# USB.net
KiCad netlist of a schematic drawn in Altium Designer
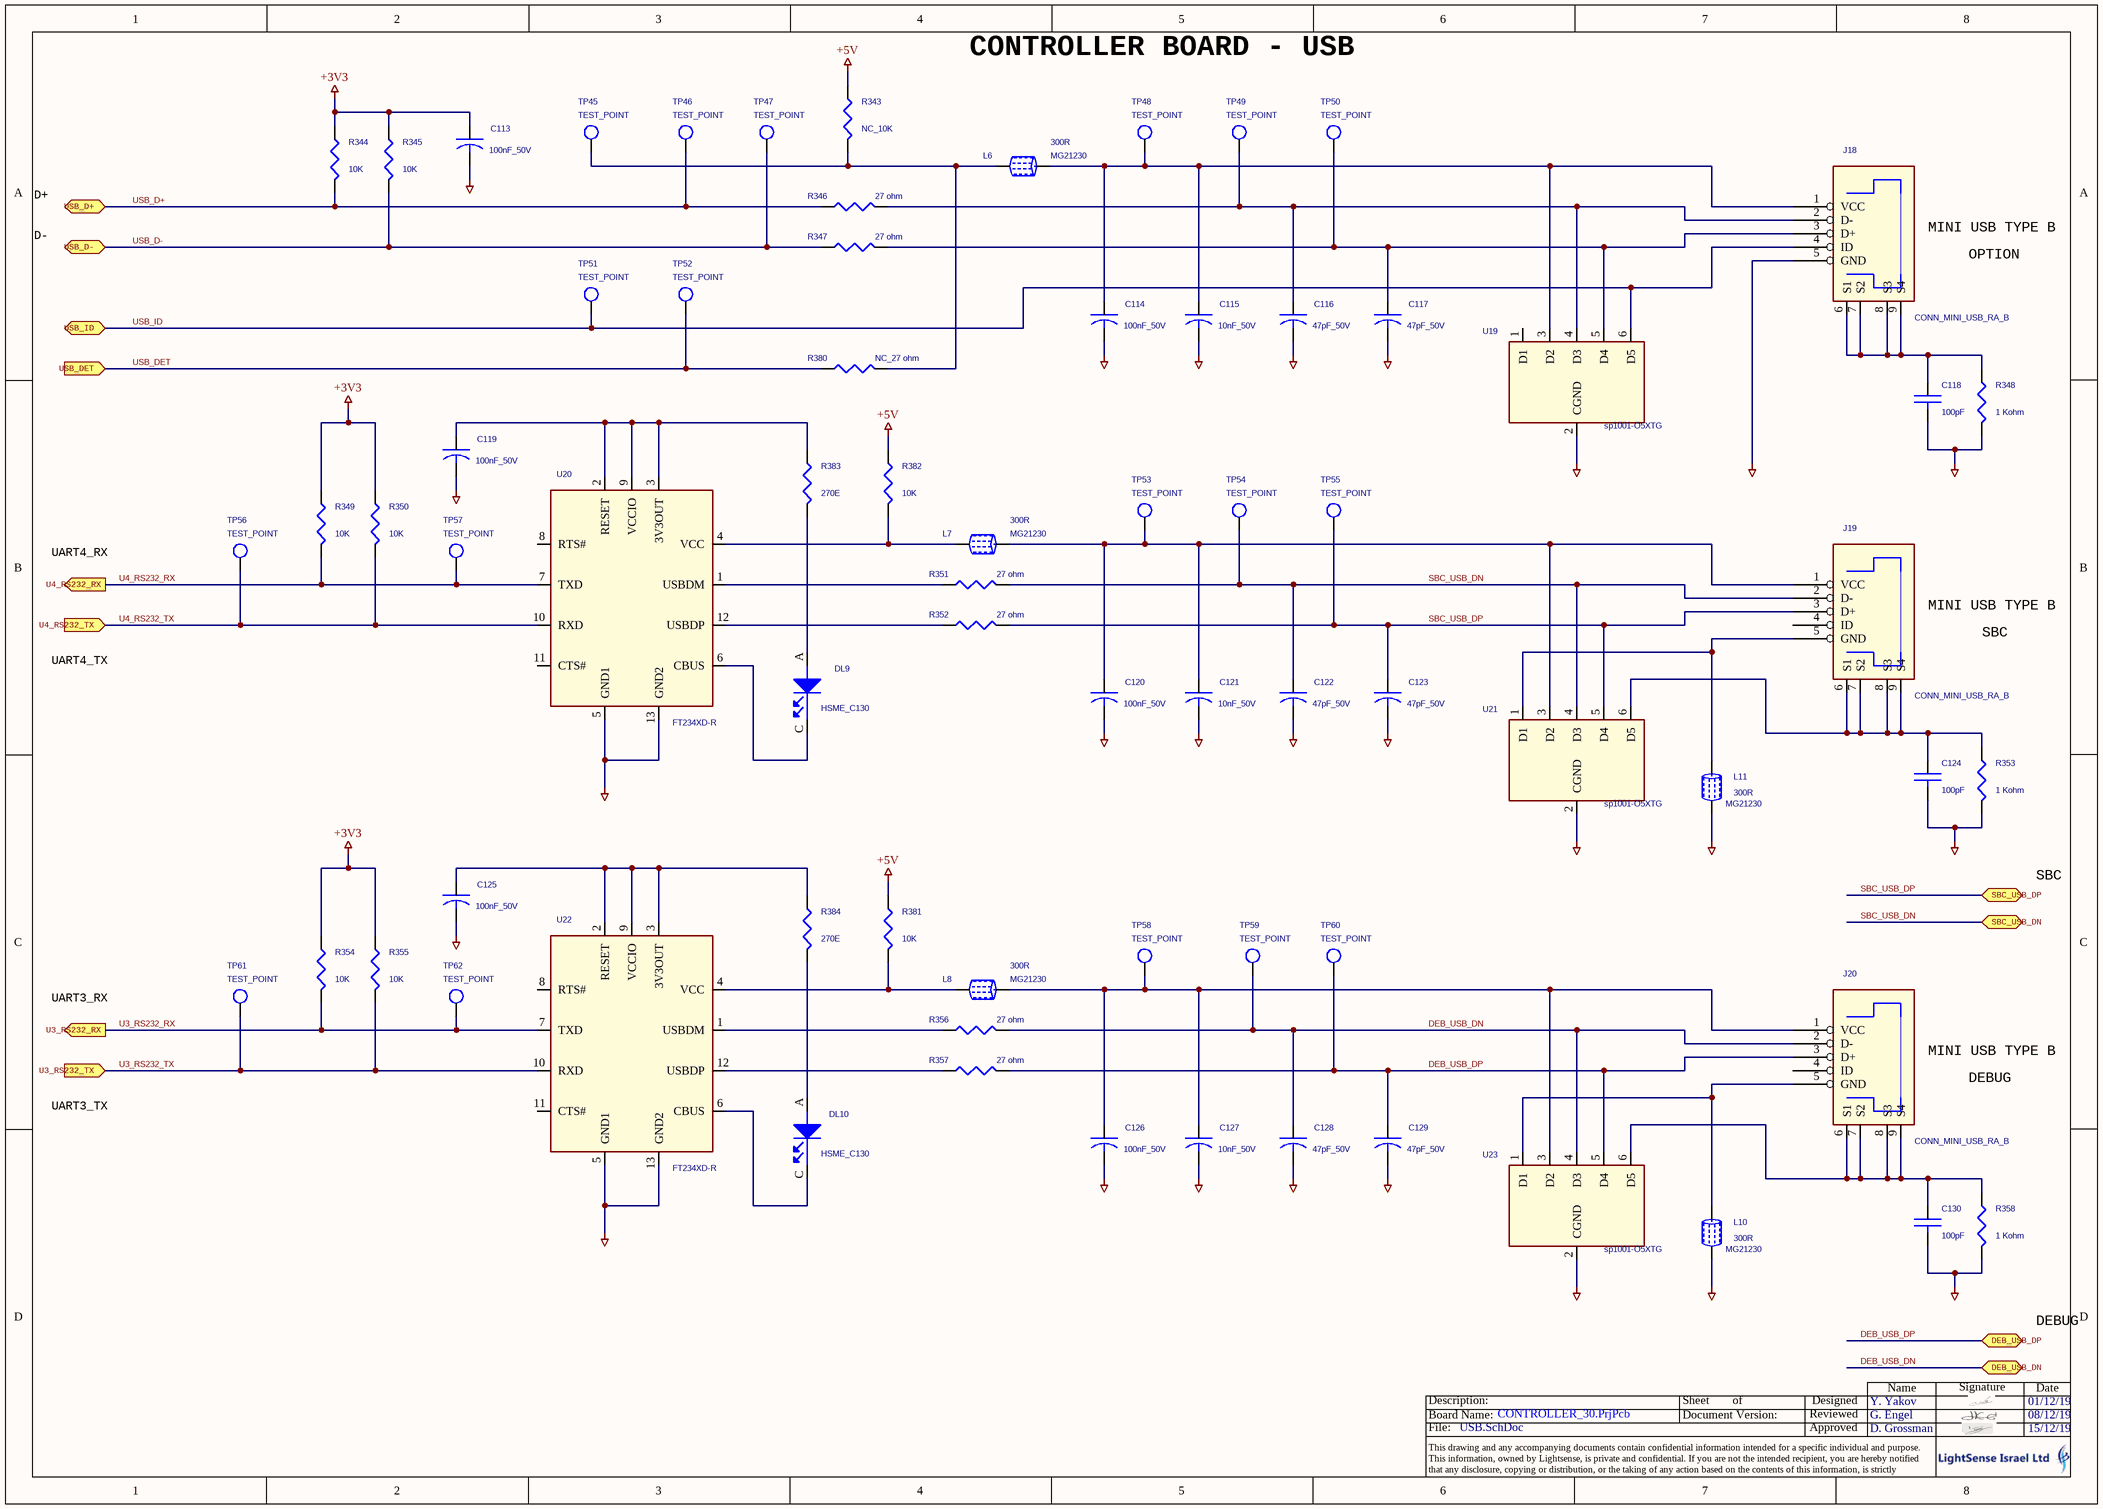
[diagram p0: USB.SchDoc]

(export (version "E")
  (design (tool "Eeschema 10.0.6"))
  (components
    (comp (ref "C113")
      (value "100nF_50V")
      (footprint "0603")
      (description "CAP_SMT_0603_50V_X7R_10%")
      (fields (field (name "MFG") "KEMET"))
      (libsource (lib "*") (part "C"))
    )
    (comp (ref "C114")
      (value "100nF_50V")
      (footprint "0603")
      (description "CAP_SMT_0603_50V_X7R_10%")
      (fields (field (name "MFG") "KEMET"))
      (libsource (lib "*") (part "C"))
    )
    (comp (ref "C115")
      (value "10nF_50V")
      (footprint "0603")
      (description "CAP_SMT_0603_50V_X7R_10%")
      (fields (field (name "MFG") "KEMET"))
      (libsource (lib "*") (part "C"))
    )
    (comp (ref "C116")
      (value "47pF_50V")
      (footprint "0603")
      (description "CAP_SMT_0603_50V_X7R_10%")
      (fields (field (name "MFG") "KEMET"))
      (libsource (lib "*") (part "C"))
    )
    (comp (ref "C117")
      (value "47pF_50V")
      (footprint "0603")
      (description "CAP_SMT_0603_50V_X7R_10%")
      (fields (field (name "MFG") "KEMET"))
      (libsource (lib "*") (part "C"))
    )
    (comp (ref "C118")
      (value "100pF")
      (footprint "C1206")
      (description "Cap cer 100pF 5% 500V C0G 1206 smd")
      (fields (field (name "PART_NUMBER") "CP70050"))
      (libsource (lib "*") (part "C1206"))
    )
    (comp (ref "C119")
      (value "100nF_50V")
      (footprint "0603")
      (description "CAP_SMT_0603_50V_X7R_10%")
      (fields (field (name "MFG") "KEMET"))
      (libsource (lib "*") (part "C"))
    )
    (comp (ref "C120")
      (value "100nF_50V")
      (footprint "0603")
      (description "CAP_SMT_0603_50V_X7R_10%")
      (fields (field (name "MFG") "KEMET"))
      (libsource (lib "*") (part "C"))
    )
    (comp (ref "C121")
      (value "10nF_50V")
      (footprint "0603")
      (description "CAP_SMT_0603_50V_X7R_10%")
      (fields (field (name "MFG") "KEMET"))
      (libsource (lib "*") (part "C"))
    )
    (comp (ref "C122")
      (value "47pF_50V")
      (footprint "0603")
      (description "CAP_SMT_0603_50V_X7R_10%")
      (fields (field (name "MFG") "KEMET"))
      (libsource (lib "*") (part "C"))
    )
    (comp (ref "C123")
      (value "47pF_50V")
      (footprint "0603")
      (description "CAP_SMT_0603_50V_X7R_10%")
      (fields (field (name "MFG") "KEMET"))
      (libsource (lib "*") (part "C"))
    )
    (comp (ref "C124")
      (value "100pF")
      (footprint "C1206")
      (description "Cap cer 100pF 5% 500V C0G 1206 smd")
      (fields (field (name "PART_NUMBER") "CP70050"))
      (libsource (lib "*") (part "C1206"))
    )
    (comp (ref "C125")
      (value "100nF_50V")
      (footprint "0603")
      (description "CAP_SMT_0603_50V_X7R_10%")
      (fields (field (name "MFG") "KEMET"))
      (libsource (lib "*") (part "C"))
    )
    (comp (ref "C126")
      (value "100nF_50V")
      (footprint "0603")
      (description "CAP_SMT_0603_50V_X7R_10%")
      (fields (field (name "MFG") "KEMET"))
      (libsource (lib "*") (part "C"))
    )
    (comp (ref "C127")
      (value "10nF_50V")
      (footprint "0603")
      (description "CAP_SMT_0603_50V_X7R_10%")
      (fields (field (name "MFG") "KEMET"))
      (libsource (lib "*") (part "C"))
    )
    (comp (ref "C128")
      (value "47pF_50V")
      (footprint "0603")
      (description "CAP_SMT_0603_50V_X7R_10%")
      (fields (field (name "MFG") "KEMET"))
      (libsource (lib "*") (part "C"))
    )
    (comp (ref "C129")
      (value "47pF_50V")
      (footprint "0603")
      (description "CAP_SMT_0603_50V_X7R_10%")
      (fields (field (name "MFG") "KEMET"))
      (libsource (lib "*") (part "C"))
    )
    (comp (ref "C130")
      (value "100pF")
      (footprint "C1206")
      (description "Cap cer 100pF 5% 500V C0G 1206 smd")
      (fields (field (name "PART_NUMBER") "CP70050"))
      (libsource (lib "*") (part "C1206"))
    )
    (comp (ref "DL9")
      (value "HSME_C130")
      (footprint "LED_0603")
      (fields (field (name "MFG") "AVAGO"))
      (libsource (lib "*") (part "LED"))
    )
    (comp (ref "DL10")
      (value "HSME_C130")
      (footprint "LED_0603")
      (fields (field (name "MFG") "AVAGO"))
      (libsource (lib "*") (part "LED"))
    )
    (comp (ref "J18")
      (value "CONN_MINI_USB_RA_B")
      (footprint "MUSB_B_9PIN")
      (fields (field (name "MFG") "SAMTEC"))
      (libsource (lib "*") (part "CONN_MINI_USB_RA_B"))
    )
    (comp (ref "J19")
      (value "CONN_MINI_USB_RA_B")
      (footprint "MUSB_B_9PIN")
      (fields (field (name "MFG") "SAMTEC"))
      (libsource (lib "*") (part "CONN_MINI_USB_RA_B"))
    )
    (comp (ref "J20")
      (value "CONN_MINI_USB_RA_B")
      (footprint "MUSB_B_9PIN")
      (fields (field (name "MFG") "SAMTEC"))
      (libsource (lib "*") (part "CONN_MINI_USB_RA_B"))
    )
    (comp (ref "L6")
      (value "300R")
      (footprint "B0603")
      (description "Chip Bead Z 300 Ohm 0603 RoHS")
      (fields (field (name "PART_NUMBER") "MG21230"))
      (libsource (lib "*") (part "FERRITE BEAD2_0"))
    )
    (comp (ref "L7")
      (value "300R")
      (footprint "B0603")
      (description "Chip Bead Z 300 Ohm 0603 RoHS")
      (fields (field (name "PART_NUMBER") "MG21230"))
      (libsource (lib "*") (part "FERRITE BEAD2_0"))
    )
    (comp (ref "L8")
      (value "300R")
      (footprint "B0603")
      (description "Chip Bead Z 300 Ohm 0603 RoHS")
      (fields (field (name "PART_NUMBER") "MG21230"))
      (libsource (lib "*") (part "FERRITE BEAD2_0"))
    )
    (comp (ref "L10")
      (value "300R")
      (footprint "B0603")
      (description "Chip Bead Z 300 Ohm 0603 RoHS")
      (fields (field (name "PART_NUMBER") "MG21230"))
      (libsource (lib "*") (part "FERRITE BEAD2_0"))
    )
    (comp (ref "L11")
      (value "300R")
      (footprint "B0603")
      (description "Chip Bead Z 300 Ohm 0603 RoHS")
      (fields (field (name "PART_NUMBER") "MG21230"))
      (libsource (lib "*") (part "FERRITE BEAD2_0"))
    )
    (comp (ref "R343")
      (value "NC_10K")
      (footprint "0603")
      (fields (field (name "MFG") "YAGEO"))
      (libsource (lib "*") (part "R_Dup1"))
    )
    (comp (ref "R344")
      (value "10K")
      (footprint "0603")
      (fields (field (name "MFG") "YAGEO"))
      (libsource (lib "*") (part "R_Dup1"))
    )
    (comp (ref "R345")
      (value "10K")
      (footprint "0603")
      (fields (field (name "MFG") "YAGEO"))
      (libsource (lib "*") (part "R_Dup1"))
    )
    (comp (ref "R346")
      (value "27 ohm")
      (footprint "R0603")
      (description "Res 330 Ohm 5% 0603 RoHS")
      (fields (field (name "PART_NUMBER") "RS61410"))
      (libsource (lib "*") (part "R0603"))
    )
    (comp (ref "R347")
      (value "27 ohm")
      (footprint "R0603")
      (description "Res 330 Ohm 5% 0603 RoHS")
      (fields (field (name "PART_NUMBER") "RS61410"))
      (libsource (lib "*") (part "R0603"))
    )
    (comp (ref "R348")
      (value "1 Kohm")
      (footprint "R1206")
      (description "RES 1 Kohm 1% 1206 RoHS")
      (fields (field (name "PART_NUMBER") "RS00940"))
      (libsource (lib "*") (part "R1206"))
    )
    (comp (ref "R349")
      (value "10K")
      (footprint "0603")
      (fields (field (name "MFG") "YAGEO"))
      (libsource (lib "*") (part "R_Dup1"))
    )
    (comp (ref "R350")
      (value "10K")
      (footprint "0603")
      (fields (field (name "MFG") "YAGEO"))
      (libsource (lib "*") (part "R_Dup1"))
    )
    (comp (ref "R351")
      (value "27 ohm")
      (footprint "R0603")
      (description "Res 330 Ohm 5% 0603 RoHS")
      (fields (field (name "PART_NUMBER") "RS61410"))
      (libsource (lib "*") (part "R0603"))
    )
    (comp (ref "R352")
      (value "27 ohm")
      (footprint "R0603")
      (description "Res 330 Ohm 5% 0603 RoHS")
      (fields (field (name "PART_NUMBER") "RS61410"))
      (libsource (lib "*") (part "R0603"))
    )
    (comp (ref "R353")
      (value "1 Kohm")
      (footprint "R1206")
      (description "RES 1 Kohm 1% 1206 RoHS")
      (fields (field (name "PART_NUMBER") "RS00940"))
      (libsource (lib "*") (part "R1206"))
    )
    (comp (ref "R354")
      (value "10K")
      (footprint "0603")
      (fields (field (name "MFG") "YAGEO"))
      (libsource (lib "*") (part "R_Dup1"))
    )
    (comp (ref "R355")
      (value "10K")
      (footprint "0603")
      (fields (field (name "MFG") "YAGEO"))
      (libsource (lib "*") (part "R_Dup1"))
    )
    (comp (ref "R356")
      (value "27 ohm")
      (footprint "R0603")
      (description "Res 330 Ohm 5% 0603 RoHS")
      (fields (field (name "PART_NUMBER") "RS61410"))
      (libsource (lib "*") (part "R0603"))
    )
    (comp (ref "R357")
      (value "27 ohm")
      (footprint "R0603")
      (description "Res 330 Ohm 5% 0603 RoHS")
      (fields (field (name "PART_NUMBER") "RS61410"))
      (libsource (lib "*") (part "R0603"))
    )
    (comp (ref "R358")
      (value "1 Kohm")
      (footprint "R1206")
      (description "RES 1 Kohm 1% 1206 RoHS")
      (fields (field (name "PART_NUMBER") "RS00940"))
      (libsource (lib "*") (part "R1206"))
    )
    (comp (ref "R380")
      (value "NC_27 ohm")
      (footprint "R0603")
      (description "Res 330 Ohm 5% 0603 RoHS")
      (fields (field (name "PART_NUMBER") "RS61410"))
      (libsource (lib "*") (part "R0603"))
    )
    (comp (ref "R381")
      (value "10K")
      (footprint "0603")
      (fields (field (name "MFG") "YAGEO"))
      (libsource (lib "*") (part "R_Dup1"))
    )
    (comp (ref "R382")
      (value "10K")
      (footprint "0603")
      (fields (field (name "MFG") "YAGEO"))
      (libsource (lib "*") (part "R_Dup1"))
    )
    (comp (ref "R383")
      (value "270E")
      (footprint "0603")
      (fields (field (name "MFG") "YAGEO"))
      (libsource (lib "*") (part "R_Dup1"))
    )
    (comp (ref "R384")
      (value "270E")
      (footprint "0603")
      (fields (field (name "MFG") "YAGEO"))
      (libsource (lib "*") (part "R_Dup1"))
    )
    (comp (ref "TP45")
      (value "TEST_POINT")
      (footprint "TH_1mm")
      (libsource (lib "*") (part "T POINT R_Dup1"))
    )
    (comp (ref "TP46")
      (value "TEST_POINT")
      (footprint "TH_1mm")
      (libsource (lib "*") (part "T POINT R_Dup1"))
    )
    (comp (ref "TP47")
      (value "TEST_POINT")
      (footprint "TH_1mm")
      (libsource (lib "*") (part "T POINT R_Dup1"))
    )
    (comp (ref "TP48")
      (value "TEST_POINT")
      (footprint "TH_1mm")
      (libsource (lib "*") (part "T POINT R_Dup1"))
    )
    (comp (ref "TP49")
      (value "TEST_POINT")
      (footprint "TH_1mm")
      (libsource (lib "*") (part "T POINT R_Dup1"))
    )
    (comp (ref "TP50")
      (value "TEST_POINT")
      (footprint "TH_1mm")
      (libsource (lib "*") (part "T POINT R_Dup1"))
    )
    (comp (ref "TP51")
      (value "TEST_POINT")
      (footprint "TH_1mm")
      (libsource (lib "*") (part "T POINT R_Dup1"))
    )
    (comp (ref "TP52")
      (value "TEST_POINT")
      (footprint "TH_1mm")
      (libsource (lib "*") (part "T POINT R_Dup1"))
    )
    (comp (ref "TP53")
      (value "TEST_POINT")
      (footprint "TH_1mm")
      (libsource (lib "*") (part "T POINT R_Dup1"))
    )
    (comp (ref "TP54")
      (value "TEST_POINT")
      (footprint "TH_1mm")
      (libsource (lib "*") (part "T POINT R_Dup1"))
    )
    (comp (ref "TP55")
      (value "TEST_POINT")
      (footprint "TH_1mm")
      (libsource (lib "*") (part "T POINT R_Dup1"))
    )
    (comp (ref "TP56")
      (value "TEST_POINT")
      (footprint "TH_1mm")
      (libsource (lib "*") (part "T POINT R_Dup1"))
    )
    (comp (ref "TP57")
      (value "TEST_POINT")
      (footprint "TH_1mm")
      (libsource (lib "*") (part "T POINT R_Dup1"))
    )
    (comp (ref "TP58")
      (value "TEST_POINT")
      (footprint "TH_1mm")
      (libsource (lib "*") (part "T POINT R_Dup1"))
    )
    (comp (ref "TP59")
      (value "TEST_POINT")
      (footprint "TH_1mm")
      (libsource (lib "*") (part "T POINT R_Dup1"))
    )
    (comp (ref "TP60")
      (value "TEST_POINT")
      (footprint "TH_1mm")
      (libsource (lib "*") (part "T POINT R_Dup1"))
    )
    (comp (ref "TP61")
      (value "TEST_POINT")
      (footprint "TH_1mm")
      (libsource (lib "*") (part "T POINT R_Dup1"))
    )
    (comp (ref "TP62")
      (value "TEST_POINT")
      (footprint "TH_1mm")
      (libsource (lib "*") (part "T POINT R_Dup1"))
    )
    (comp (ref "U19")
      (value "sp1001-O5XTG")
      (footprint "SOT_563")
      (libsource (lib "*") (part "sp1001-O5XTG"))
    )
    (comp (ref "U20")
      (value "FT234XD-R")
      (footprint "DFN_13")
      (fields (field (name "MFG") "FTDI"))
      (libsource (lib "*") (part "FT234XD-R_1"))
    )
    (comp (ref "U21")
      (value "sp1001-O5XTG")
      (footprint "SOT_563")
      (libsource (lib "*") (part "sp1001-O5XTG"))
    )
    (comp (ref "U22")
      (value "FT234XD-R")
      (footprint "DFN_13")
      (fields (field (name "MFG") "FTDI"))
      (libsource (lib "*") (part "FT234XD-R_1"))
    )
    (comp (ref "U23")
      (value "sp1001-O5XTG")
      (footprint "SOT_563")
      (libsource (lib "*") (part "sp1001-O5XTG"))
    )
  )
  (nets
    (net (code "1") (name "+3V3") (class "Default")
      (node (ref "C113") (pin "1") (pinfunction "1_1") (pintype "passive"))
      (node (ref "R344") (pin "1") (pinfunction "1_1") (pintype "passive"))
      (node (ref "R345") (pin "1") (pinfunction "1_1") (pintype "passive"))
      (node (ref "R349") (pin "1") (pinfunction "1_1") (pintype "passive"))
      (node (ref "R350") (pin "1") (pinfunction "1_1") (pintype "passive"))
      (node (ref "R354") (pin "1") (pinfunction "1_1") (pintype "passive"))
      (node (ref "R355") (pin "1") (pinfunction "1_1") (pintype "passive"))
    )
    (net (code "2") (name "+5V") (class "Default")
      (node (ref "R343") (pin "1") (pinfunction "1_1") (pintype "passive"))
      (node (ref "R381") (pin "1") (pinfunction "1_1") (pintype "passive"))
      (node (ref "R382") (pin "1") (pinfunction "1_1") (pintype "passive"))
    )
    (net (code "3") (name "/DEB_USB_DN") (class "Default")
      (node (ref "C128") (pin "1") (pinfunction "1_1") (pintype "passive"))
      (node (ref "J20") (pin "2") (pinfunction "D-_2") (pintype "passive"))
      (node (ref "R356") (pin "2") (pinfunction "2_2") (pintype "passive"))
      (node (ref "TP59") (pin "1") (pinfunction "TP_1") (pintype "passive"))
      (node (ref "U23") (pin "4") (pinfunction "D3_4") (pintype "passive"))
    )
    (net (code "4") (name "/DEB_USB_DP") (class "Default")
      (node (ref "C129") (pin "1") (pinfunction "1_1") (pintype "passive"))
      (node (ref "J20") (pin "3") (pinfunction "D+_3") (pintype "passive"))
      (node (ref "R357") (pin "2") (pinfunction "2_2") (pintype "passive"))
      (node (ref "TP60") (pin "1") (pinfunction "TP_1") (pintype "passive"))
      (node (ref "U23") (pin "5") (pinfunction "D4_5") (pintype "passive"))
    )
    (net (code "5") (name "/SBC_USB_DN") (class "Default")
      (node (ref "C122") (pin "1") (pinfunction "1_1") (pintype "passive"))
      (node (ref "J19") (pin "2") (pinfunction "D-_2") (pintype "passive"))
      (node (ref "R351") (pin "2") (pinfunction "2_2") (pintype "passive"))
      (node (ref "TP54") (pin "1") (pinfunction "TP_1") (pintype "passive"))
      (node (ref "U21") (pin "4") (pinfunction "D3_4") (pintype "passive"))
    )
    (net (code "6") (name "/SBC_USB_DP") (class "Default")
      (node (ref "C123") (pin "1") (pinfunction "1_1") (pintype "passive"))
      (node (ref "J19") (pin "3") (pinfunction "D+_3") (pintype "passive"))
      (node (ref "R352") (pin "2") (pinfunction "2_2") (pintype "passive"))
      (node (ref "TP55") (pin "1") (pinfunction "TP_1") (pintype "passive"))
      (node (ref "U21") (pin "5") (pinfunction "D4_5") (pintype "passive"))
    )
    (net (code "7") (name "/U3_RS232_RX") (class "Default")
      (node (ref "R354") (pin "2") (pinfunction "2_2") (pintype "passive"))
      (node (ref "TP62") (pin "1") (pinfunction "TP_1") (pintype "passive"))
      (node (ref "U22") (pin "7") (pinfunction "TXD_7") (pintype "passive"))
    )
    (net (code "8") (name "/U3_RS232_TX") (class "Default")
      (node (ref "R355") (pin "2") (pinfunction "2_2") (pintype "passive"))
      (node (ref "TP61") (pin "1") (pinfunction "TP_1") (pintype "passive"))
      (node (ref "U22") (pin "10") (pinfunction "RXD_10") (pintype "passive"))
    )
    (net (code "9") (name "/U4_RS232_RX") (class "Default")
      (node (ref "R349") (pin "2") (pinfunction "2_2") (pintype "passive"))
      (node (ref "TP57") (pin "1") (pinfunction "TP_1") (pintype "passive"))
      (node (ref "U20") (pin "7") (pinfunction "TXD_7") (pintype "passive"))
    )
    (net (code "10") (name "/U4_RS232_TX") (class "Default")
      (node (ref "R350") (pin "2") (pinfunction "2_2") (pintype "passive"))
      (node (ref "TP56") (pin "1") (pinfunction "TP_1") (pintype "passive"))
      (node (ref "U20") (pin "10") (pinfunction "RXD_10") (pintype "passive"))
    )
    (net (code "11") (name "/USB_D+") (class "Default")
      (node (ref "R344") (pin "2") (pinfunction "2_2") (pintype "passive"))
      (node (ref "R346") (pin "1") (pinfunction "1_1") (pintype "passive"))
      (node (ref "TP46") (pin "1") (pinfunction "TP_1") (pintype "passive"))
    )
    (net (code "12") (name "/USB_D-") (class "Default")
      (node (ref "R345") (pin "2") (pinfunction "2_2") (pintype "passive"))
      (node (ref "R347") (pin "1") (pinfunction "1_1") (pintype "passive"))
      (node (ref "TP47") (pin "1") (pinfunction "TP_1") (pintype "passive"))
    )
    (net (code "13") (name "/USB_DET") (class "Default")
      (node (ref "R380") (pin "1") (pinfunction "1_1") (pintype "passive"))
      (node (ref "TP52") (pin "1") (pinfunction "TP_1") (pintype "passive"))
    )
    (net (code "14") (name "/USB_ID") (class "Default")
      (node (ref "J18") (pin "4") (pinfunction "ID_4") (pintype "passive"))
      (node (ref "TP51") (pin "1") (pinfunction "TP_1") (pintype "passive"))
      (node (ref "U19") (pin "6") (pinfunction "D5_6") (pintype "passive"))
    )
    (net (code "15") (name "GND_CPU") (class "Default")
      (node (ref "C113") (pin "2") (pinfunction "2_2") (pintype "passive"))
      (node (ref "C114") (pin "2") (pinfunction "2_2") (pintype "passive"))
      (node (ref "C115") (pin "2") (pinfunction "2_2") (pintype "passive"))
      (node (ref "C116") (pin "2") (pinfunction "2_2") (pintype "passive"))
      (node (ref "C117") (pin "2") (pinfunction "2_2") (pintype "passive"))
      (node (ref "C118") (pin "2") (pinfunction "2_2") (pintype "passive"))
      (node (ref "C119") (pin "2") (pinfunction "2_2") (pintype "passive"))
      (node (ref "C120") (pin "2") (pinfunction "2_2") (pintype "passive"))
      (node (ref "C121") (pin "2") (pinfunction "2_2") (pintype "passive"))
      (node (ref "C122") (pin "2") (pinfunction "2_2") (pintype "passive"))
      (node (ref "C123") (pin "2") (pinfunction "2_2") (pintype "passive"))
      (node (ref "C124") (pin "2") (pinfunction "2_2") (pintype "passive"))
      (node (ref "C125") (pin "2") (pinfunction "2_2") (pintype "passive"))
      (node (ref "C126") (pin "2") (pinfunction "2_2") (pintype "passive"))
      (node (ref "C127") (pin "2") (pinfunction "2_2") (pintype "passive"))
      (node (ref "C128") (pin "2") (pinfunction "2_2") (pintype "passive"))
      (node (ref "C129") (pin "2") (pinfunction "2_2") (pintype "passive"))
      (node (ref "C130") (pin "2") (pinfunction "2_2") (pintype "passive"))
      (node (ref "J18") (pin "5") (pinfunction "GND_5") (pintype "passive"))
      (node (ref "L10") (pin "1") (pinfunction "1_1") (pintype "passive"))
      (node (ref "L11") (pin "1") (pinfunction "1_1") (pintype "passive"))
      (node (ref "R348") (pin "2") (pinfunction "2_2") (pintype "passive"))
      (node (ref "R353") (pin "2") (pinfunction "2_2") (pintype "passive"))
      (node (ref "R358") (pin "2") (pinfunction "2_2") (pintype "passive"))
      (node (ref "U19") (pin "2") (pinfunction "CGND_2") (pintype "passive"))
      (node (ref "U20") (pin "13") (pinfunction "GND2_13") (pintype "passive"))
      (node (ref "U20") (pin "5") (pinfunction "GND1_5") (pintype "passive"))
      (node (ref "U21") (pin "2") (pinfunction "CGND_2") (pintype "passive"))
      (node (ref "U22") (pin "13") (pinfunction "GND2_13") (pintype "passive"))
      (node (ref "U22") (pin "5") (pinfunction "GND1_5") (pintype "passive"))
      (node (ref "U23") (pin "2") (pinfunction "CGND_2") (pintype "passive"))
    )
    (net (code "16") (name "Net-(DL9-ANODE)") (class "Default")
      (node (ref "DL9") (pin "A") (pinfunction "ANODE_A") (pintype "passive"))
      (node (ref "R383") (pin "2") (pinfunction "2_2") (pintype "passive"))
    )
    (net (code "17") (name "Net-(DL9-CATHODE)") (class "Default")
      (node (ref "DL9") (pin "C") (pinfunction "CATHODE_C") (pintype "passive"))
      (node (ref "U20") (pin "6") (pinfunction "CBUS_6") (pintype "passive"))
    )
    (net (code "18") (name "Net-(DL10-ANODE)") (class "Default")
      (node (ref "DL10") (pin "A") (pinfunction "ANODE_A") (pintype "passive"))
      (node (ref "R384") (pin "2") (pinfunction "2_2") (pintype "passive"))
    )
    (net (code "19") (name "Net-(DL10-CATHODE)") (class "Default")
      (node (ref "DL10") (pin "C") (pinfunction "CATHODE_C") (pintype "passive"))
      (node (ref "U22") (pin "6") (pinfunction "CBUS_6") (pintype "passive"))
    )
    (net (code "20") (name "Net-(J18-D+)") (class "Default")
      (node (ref "C117") (pin "1") (pinfunction "1_1") (pintype "passive"))
      (node (ref "J18") (pin "3") (pinfunction "D+_3") (pintype "passive"))
      (node (ref "R347") (pin "2") (pinfunction "2_2") (pintype "passive"))
      (node (ref "TP50") (pin "1") (pinfunction "TP_1") (pintype "passive"))
      (node (ref "U19") (pin "5") (pinfunction "D4_5") (pintype "passive"))
    )
    (net (code "21") (name "Net-(J18-D-)") (class "Default")
      (node (ref "C116") (pin "1") (pinfunction "1_1") (pintype "passive"))
      (node (ref "J18") (pin "2") (pinfunction "D-_2") (pintype "passive"))
      (node (ref "R346") (pin "2") (pinfunction "2_2") (pintype "passive"))
      (node (ref "TP49") (pin "1") (pinfunction "TP_1") (pintype "passive"))
      (node (ref "U19") (pin "4") (pinfunction "D3_4") (pintype "passive"))
    )
    (net (code "22") (name "Net-(J18-S1)") (class "Default")
      (node (ref "C118") (pin "1") (pinfunction "1_1") (pintype "passive"))
      (node (ref "J18") (pin "6") (pinfunction "S1_6") (pintype "passive"))
      (node (ref "J18") (pin "7") (pinfunction "S2_7") (pintype "passive"))
      (node (ref "J18") (pin "8") (pinfunction "S3_8") (pintype "passive"))
      (node (ref "J18") (pin "9") (pinfunction "S4_9") (pintype "passive"))
      (node (ref "R348") (pin "1") (pinfunction "1_1") (pintype "passive"))
    )
    (net (code "23") (name "Net-(J18-VCC)") (class "Default")
      (node (ref "C114") (pin "1") (pinfunction "1_1") (pintype "passive"))
      (node (ref "C115") (pin "1") (pinfunction "1_1") (pintype "passive"))
      (node (ref "J18") (pin "1") (pinfunction "VCC_1") (pintype "passive"))
      (node (ref "L6") (pin "2") (pinfunction "2_2") (pintype "passive"))
      (node (ref "TP48") (pin "1") (pinfunction "TP_1") (pintype "passive"))
      (node (ref "U19") (pin "3") (pinfunction "D2_3") (pintype "passive"))
    )
    (net (code "24") (name "Net-(J19-GND)") (class "Default")
      (node (ref "J19") (pin "5") (pinfunction "GND_5") (pintype "passive"))
      (node (ref "L11") (pin "2") (pinfunction "2_2") (pintype "passive"))
      (node (ref "U21") (pin "1") (pinfunction "D1_1") (pintype "passive"))
    )
    (net (code "25") (name "Net-(J19-S1)") (class "Default")
      (node (ref "C124") (pin "1") (pinfunction "1_1") (pintype "passive"))
      (node (ref "J19") (pin "6") (pinfunction "S1_6") (pintype "passive"))
      (node (ref "J19") (pin "7") (pinfunction "S2_7") (pintype "passive"))
      (node (ref "J19") (pin "8") (pinfunction "S3_8") (pintype "passive"))
      (node (ref "J19") (pin "9") (pinfunction "S4_9") (pintype "passive"))
      (node (ref "R353") (pin "1") (pinfunction "1_1") (pintype "passive"))
      (node (ref "U21") (pin "6") (pinfunction "D5_6") (pintype "passive"))
    )
    (net (code "26") (name "Net-(J19-VCC)") (class "Default")
      (node (ref "C120") (pin "1") (pinfunction "1_1") (pintype "passive"))
      (node (ref "C121") (pin "1") (pinfunction "1_1") (pintype "passive"))
      (node (ref "J19") (pin "1") (pinfunction "VCC_1") (pintype "passive"))
      (node (ref "L7") (pin "2") (pinfunction "2_2") (pintype "passive"))
      (node (ref "TP53") (pin "1") (pinfunction "TP_1") (pintype "passive"))
      (node (ref "U21") (pin "3") (pinfunction "D2_3") (pintype "passive"))
    )
    (net (code "27") (name "Net-(J20-GND)") (class "Default")
      (node (ref "J20") (pin "5") (pinfunction "GND_5") (pintype "passive"))
      (node (ref "L10") (pin "2") (pinfunction "2_2") (pintype "passive"))
      (node (ref "U23") (pin "1") (pinfunction "D1_1") (pintype "passive"))
    )
    (net (code "28") (name "Net-(J20-S1)") (class "Default")
      (node (ref "C130") (pin "1") (pinfunction "1_1") (pintype "passive"))
      (node (ref "J20") (pin "6") (pinfunction "S1_6") (pintype "passive"))
      (node (ref "J20") (pin "7") (pinfunction "S2_7") (pintype "passive"))
      (node (ref "J20") (pin "8") (pinfunction "S3_8") (pintype "passive"))
      (node (ref "J20") (pin "9") (pinfunction "S4_9") (pintype "passive"))
      (node (ref "R358") (pin "1") (pinfunction "1_1") (pintype "passive"))
      (node (ref "U23") (pin "6") (pinfunction "D5_6") (pintype "passive"))
    )
    (net (code "29") (name "Net-(J20-VCC)") (class "Default")
      (node (ref "C126") (pin "1") (pinfunction "1_1") (pintype "passive"))
      (node (ref "C127") (pin "1") (pinfunction "1_1") (pintype "passive"))
      (node (ref "J20") (pin "1") (pinfunction "VCC_1") (pintype "passive"))
      (node (ref "L8") (pin "2") (pinfunction "2_2") (pintype "passive"))
      (node (ref "TP58") (pin "1") (pinfunction "TP_1") (pintype "passive"))
      (node (ref "U23") (pin "3") (pinfunction "D2_3") (pintype "passive"))
    )
    (net (code "30") (name "Net-(TP45-TP)") (class "Default")
      (node (ref "L6") (pin "1") (pinfunction "1_1") (pintype "passive"))
      (node (ref "R343") (pin "2") (pinfunction "2_2") (pintype "passive"))
      (node (ref "R380") (pin "2") (pinfunction "2_2") (pintype "passive"))
      (node (ref "TP45") (pin "1") (pinfunction "TP_1") (pintype "passive"))
    )
    (net (code "31") (name "Net-(U20-3V3OUT)") (class "Default")
      (node (ref "C119") (pin "1") (pinfunction "1_1") (pintype "passive"))
      (node (ref "R383") (pin "1") (pinfunction "1_1") (pintype "passive"))
      (node (ref "U20") (pin "2") (pinfunction "RESET_2") (pintype "passive"))
      (node (ref "U20") (pin "3") (pinfunction "3V3OUT_3") (pintype "passive"))
      (node (ref "U20") (pin "9") (pinfunction "VCCIO_9") (pintype "passive"))
    )
    (net (code "32") (name "Net-(U20-USBDM)") (class "Default")
      (node (ref "R351") (pin "1") (pinfunction "1_1") (pintype "passive"))
      (node (ref "U20") (pin "1") (pinfunction "USBDM_1") (pintype "passive"))
    )
    (net (code "33") (name "Net-(U20-USBDP)") (class "Default")
      (node (ref "R352") (pin "1") (pinfunction "1_1") (pintype "passive"))
      (node (ref "U20") (pin "12") (pinfunction "USBDP_12") (pintype "passive"))
    )
    (net (code "34") (name "Net-(U20-VCC)") (class "Default")
      (node (ref "L7") (pin "1") (pinfunction "1_1") (pintype "passive"))
      (node (ref "R382") (pin "2") (pinfunction "2_2") (pintype "passive"))
      (node (ref "U20") (pin "4") (pinfunction "VCC_4") (pintype "passive"))
    )
    (net (code "35") (name "Net-(U22-3V3OUT)") (class "Default")
      (node (ref "C125") (pin "1") (pinfunction "1_1") (pintype "passive"))
      (node (ref "R384") (pin "1") (pinfunction "1_1") (pintype "passive"))
      (node (ref "U22") (pin "2") (pinfunction "RESET_2") (pintype "passive"))
      (node (ref "U22") (pin "3") (pinfunction "3V3OUT_3") (pintype "passive"))
      (node (ref "U22") (pin "9") (pinfunction "VCCIO_9") (pintype "passive"))
    )
    (net (code "36") (name "Net-(U22-USBDM)") (class "Default")
      (node (ref "R356") (pin "1") (pinfunction "1_1") (pintype "passive"))
      (node (ref "U22") (pin "1") (pinfunction "USBDM_1") (pintype "passive"))
    )
    (net (code "37") (name "Net-(U22-USBDP)") (class "Default")
      (node (ref "R357") (pin "1") (pinfunction "1_1") (pintype "passive"))
      (node (ref "U22") (pin "12") (pinfunction "USBDP_12") (pintype "passive"))
    )
    (net (code "38") (name "Net-(U22-VCC)") (class "Default")
      (node (ref "L8") (pin "1") (pinfunction "1_1") (pintype "passive"))
      (node (ref "R381") (pin "2") (pinfunction "2_2") (pintype "passive"))
      (node (ref "U22") (pin "4") (pinfunction "VCC_4") (pintype "passive"))
    )
    (net (code "39") (name "unconnected-(J19-ID-Pad4)") (class "Default")
      (node (ref "J19") (pin "4") (pinfunction "ID_4") (pintype "passive"))
    )
    (net (code "40") (name "unconnected-(J20-ID-Pad4)") (class "Default")
      (node (ref "J20") (pin "4") (pinfunction "ID_4") (pintype "passive"))
    )
    (net (code "41") (name "unconnected-(U19-D1-Pad1)") (class "Default")
      (node (ref "U19") (pin "1") (pinfunction "D1_1") (pintype "passive"))
    )
    (net (code "42") (name "unconnected-(U20-CTS#-Pad11)") (class "Default")
      (node (ref "U20") (pin "11") (pinfunction "CTS#_11") (pintype "passive"))
    )
    (net (code "43") (name "unconnected-(U20-RTS#-Pad8)") (class "Default")
      (node (ref "U20") (pin "8") (pinfunction "RTS#_8") (pintype "passive"))
    )
    (net (code "44") (name "unconnected-(U22-CTS#-Pad11)") (class "Default")
      (node (ref "U22") (pin "11") (pinfunction "CTS#_11") (pintype "passive"))
    )
    (net (code "45") (name "unconnected-(U22-RTS#-Pad8)") (class "Default")
      (node (ref "U22") (pin "8") (pinfunction "RTS#_8") (pintype "passive"))
    )
  )
)
